# ECG_Schematic.net
KiCad netlist of a schematic drawn in Altium Designer
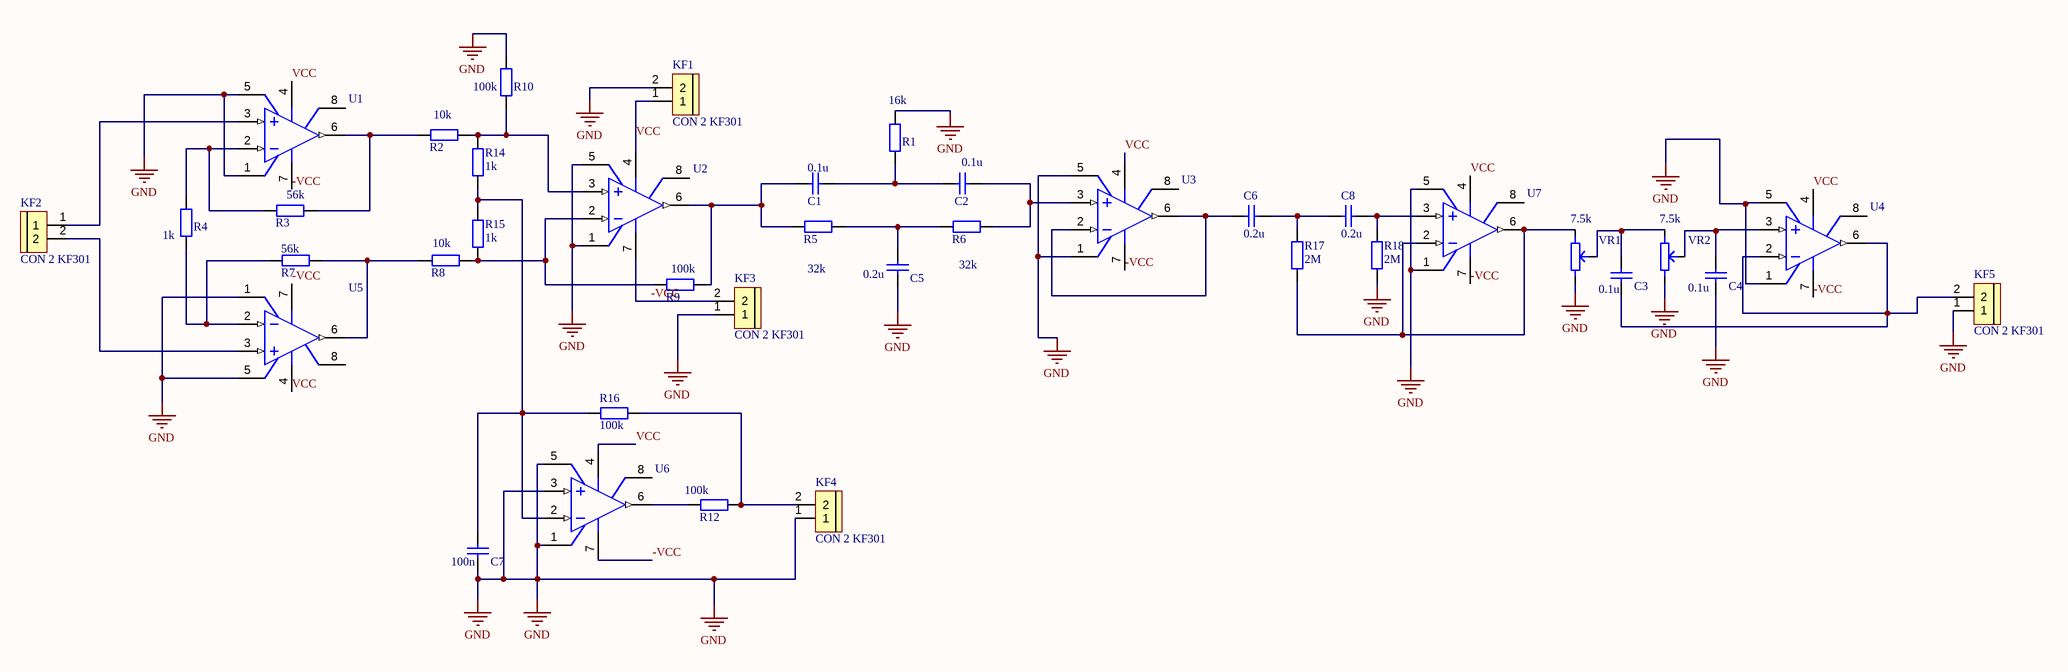
[diagram p0: ECG_Schematic_.SchDoc]

(export (version "E")
  (design (tool "Eeschema 10.0.6"))
  (components
    (comp (ref "C1")
      (value "0.1u")
      (footprint "tu gom")
      (description "C?m")
      (libsource (lib "Ho Chi Minh University of Technology") (part "Tu tantalum 47nF 50V 20 DIP5.08"))
    )
    (comp (ref "C2")
      (value "0.1u")
      (footprint "tu gom")
      (description "C?m")
      (libsource (lib "Ho Chi Minh University of Technology") (part "Tu tantalum 47nF 50V 20 DIP5.08"))
    )
    (comp (ref "C3")
      (value "0.1u")
      (footprint "tu gom")
      (description "C?m")
      (libsource (lib "Ho Chi Minh University of Technology") (part "Tu tantalum 47nF 50V 20 DIP5.08"))
    )
    (comp (ref "C4")
      (value "0.1u")
      (footprint "tu gom")
      (description "C?m")
      (libsource (lib "Ho Chi Minh University of Technology") (part "Tu tantalum 47nF 50V 20 DIP5.08"))
    )
    (comp (ref "C5")
      (value "0.2u")
      (footprint "tu gom")
      (description "C?m")
      (libsource (lib "Ho Chi Minh University of Technology") (part "Tu tantalum 47nF 50V 20 DIP5.08"))
    )
    (comp (ref "C6")
      (value "0.2u")
      (footprint "tu gom")
      (description "C?m")
      (libsource (lib "Ho Chi Minh University of Technology") (part "Tu tantalum 47nF 50V 20 DIP5.08"))
    )
    (comp (ref "C7")
      (value "100n")
      (footprint "tu gom")
      (description "C?m")
      (libsource (lib "Ho Chi Minh University of Technology") (part "Tu tantalum 47nF 50V 20 DIP5.08"))
    )
    (comp (ref "C8")
      (value "0.2u")
      (footprint "tu gom")
      (description "C?m")
      (libsource (lib "Ho Chi Minh University of Technology") (part "Tu tantalum 47nF 50V 20 DIP5.08"))
    )
    (comp (ref "KF1")
      (value "CON 2 KF301")
      (footprint "Con 2 KF301 5.08")
      (description "C?m")
      (libsource (lib "") (part "CON 2 KF7.62_1"))
    )
    (comp (ref "KF2")
      (value "CON 2 KF301")
      (footprint "Con 2 KF301 5.08")
      (description "C?m")
      (libsource (lib "Ho Chi Minh University of Technology") (part "CON 2 KF7.62"))
    )
    (comp (ref "KF3")
      (value "CON 2 KF301")
      (footprint "Con 2 KF301 5.08")
      (description "C?m")
      (libsource (lib "") (part "CON 2 KF7.62_1"))
    )
    (comp (ref "KF4")
      (value "CON 2 KF301")
      (footprint "Con 2 KF301 5.08")
      (description "Cắm")
      (libsource (lib "Connector") (part "CON 2 KF301"))
    )
    (comp (ref "KF5")
      (value "CON 2 KF301")
      (footprint "Con 2 KF301 5.08")
      (description "Cắm")
      (libsource (lib "Connector") (part "CON 2 KF301"))
    )
    (comp (ref "R1")
      (value "16k")
      (footprint "tro vach 1/4w")
      (description "C?m")
      (libsource (lib "Ho Chi Minh University of Technology") (part "Tro Vach 1/4W 5 0.11R"))
    )
    (comp (ref "R2")
      (value "10k")
      (footprint "tro vach 1/4w")
      (description "C?m")
      (libsource (lib "Ho Chi Minh University of Technology") (part "Tro Vach 1/4W 5 0.11R"))
    )
    (comp (ref "R3")
      (value "56k")
      (footprint "tro vach 1/4w")
      (description "C?m")
      (libsource (lib "Ho Chi Minh University of Technology") (part "Tro Vach 1/4W 5 0.11R"))
    )
    (comp (ref "R4")
      (value "1k")
      (footprint "tro vach 1/4w")
      (description "C?m")
      (libsource (lib "Ho Chi Minh University of Technology") (part "Tro Vach 1/4W 5 0.11R"))
    )
    (comp (ref "R5")
      (value "32k")
      (footprint "tro vach 1/4w")
      (description "C?m")
      (libsource (lib "Ho Chi Minh University of Technology") (part "Tro Vach 1/4W 5 0.11R"))
    )
    (comp (ref "R6")
      (value "32k")
      (footprint "tro vach 1/4w")
      (description "C?m")
      (libsource (lib "Ho Chi Minh University of Technology") (part "Tro Vach 1/4W 5 0.11R"))
    )
    (comp (ref "R7")
      (value "56k")
      (footprint "tro vach 1/4w")
      (description "C?m")
      (libsource (lib "Ho Chi Minh University of Technology") (part "Tro Vach 1/4W 5 0.11R"))
    )
    (comp (ref "R8")
      (value "10k")
      (footprint "tro vach 1/4w")
      (description "C?m")
      (libsource (lib "Ho Chi Minh University of Technology") (part "Tro Vach 1/4W 5 0.11R"))
    )
    (comp (ref "R9")
      (value "100k")
      (footprint "tro vach 1/4w")
      (description "C?m")
      (libsource (lib "Ho Chi Minh University of Technology") (part "Tro Vach 1/4W 5 0.11R"))
    )
    (comp (ref "R10")
      (value "100k")
      (footprint "tro vach 1/4w")
      (description "C?m")
      (libsource (lib "Ho Chi Minh University of Technology") (part "Tro Vach 1/4W 5 0.11R"))
    )
    (comp (ref "R12")
      (value "100k")
      (footprint "tro vach 1/4w")
      (description "C?m")
      (libsource (lib "Ho Chi Minh University of Technology") (part "Tro Vach 1/4W 5 0.11R"))
    )
    (comp (ref "R14")
      (value "1k")
      (footprint "tro vach 1/4w")
      (description "Cắm")
      (libsource (lib "Dien Tro") (part "Tro Vach 1/4W 1% 3k"))
    )
    (comp (ref "R15")
      (value "1k")
      (footprint "tro vach 1/4w")
      (description "Cắm")
      (libsource (lib "Dien Tro") (part "Tro Vach 1/4W 1% 3k"))
    )
    (comp (ref "R16")
      (value "100k")
      (footprint "tro vach 1/4w")
      (description "Cắm")
      (libsource (lib "Dien Tro") (part "Tro Vach 1/4W 1% 3k"))
    )
    (comp (ref "R17")
      (value "2M")
      (footprint "tro vach 1/4w")
      (description "C?m")
      (libsource (lib "Ho Chi Minh University of Technology") (part "Tro Vach 1/4W 5 0.11R"))
    )
    (comp (ref "R18")
      (value "2M")
      (footprint "tro vach 1/4w")
      (description "C?m")
      (libsource (lib "Ho Chi Minh University of Technology") (part "Tro Vach 1/4W 5 0.11R"))
    )
    (comp (ref "U1")
      (value "LM741CN/NOPB")
      (footprint "P0008A")
      (description "Operational Amplifier, 8-pin MDIP, Pb-Free")
      (fields (field (name "MANUFACTURER") "Texas Instruments"))
      (libsource (lib "Altium Content Vault") (part "AMP-OPA-LM741-8"))
    )
    (comp (ref "U2")
      (value "LM741CN/NOPB")
      (footprint "P0008A")
      (description "Operational Amplifier, 8-pin MDIP, Pb-Free")
      (fields (field (name "MANUFACTURER") "Texas Instruments"))
      (libsource (lib "Altium Content Vault") (part "AMP-OPA-LM741-8"))
    )
    (comp (ref "U3")
      (value "LM741CN/NOPB")
      (footprint "P0008A")
      (description "Operational Amplifier, 8-pin MDIP, Pb-Free")
      (fields (field (name "MANUFACTURER") "Texas Instruments"))
      (libsource (lib "Altium Content Vault") (part "AMP-OPA-LM741-8"))
    )
    (comp (ref "U4")
      (value "LM741CN/NOPB")
      (footprint "P0008A")
      (description "Operational Amplifier, 8-pin MDIP, Pb-Free")
      (fields (field (name "MANUFACTURER") "Texas Instruments"))
      (libsource (lib "Altium Content Vault") (part "AMP-OPA-LM741-8"))
    )
    (comp (ref "U5")
      (value "B")
      (footprint "P0008A")
      (description "Operational Amplifier, 8-pin MDIP, Pb-Free")
      (fields (field (name "MANUFACTURER") "Texas Instruments"))
      (libsource (lib "Altium Content Vault") (part "AMP-OPA-LM741-8"))
    )
    (comp (ref "U6")
      (value "B")
      (footprint "P0008A")
      (description "Operational Amplifier, 8-pin MDIP, Pb-Free")
      (fields (field (name "MANUFACTURER") "Texas Instruments"))
      (libsource (lib "Altium Content Vault") (part "AMP-OPA-LM741-8"))
    )
    (comp (ref "U7")
      (value "LM741CN/NOPB")
      (footprint "P0008A")
      (description "Operational Amplifier, 8-pin MDIP, Pb-Free")
      (fields (field (name "MANUFACTURER") "Texas Instruments"))
      (libsource (lib "Altium Content Vault") (part "AMP-OPA-LM741-8"))
    )
    (comp (ref "VR1")
      (value "7.5k")
      (footprint "Bien Tro Tam Giac Nam")
      (description "C?m")
      (libsource (lib "Ho Chi Minh University of Technology") (part "Bien tro tam giac 20K Dung"))
    )
    (comp (ref "VR2")
      (value "7.5k")
      (footprint "Bien Tro Tam Giac Nam")
      (description "C?m")
      (libsource (lib "Ho Chi Minh University of Technology") (part "Bien tro tam giac 20K Dung"))
    )
  )
  (nets
    (net (code "1") (name "/-VCC") (class "Default")
      (node (ref "KF3") (pin "2") (pinfunction "2_2") (pintype "passive"))
      (node (ref "U1") (pin "7") (pinfunction "V+_7") (pintype "power_in"))
      (node (ref "U2") (pin "7") (pinfunction "V+_7") (pintype "power_in"))
      (node (ref "U3") (pin "7") (pinfunction "V+_7") (pintype "power_in"))
      (node (ref "U4") (pin "7") (pinfunction "V+_7") (pintype "power_in"))
      (node (ref "U5") (pin "7") (pinfunction "V+_7") (pintype "power_in"))
      (node (ref "U6") (pin "7") (pinfunction "V+_7") (pintype "power_in"))
      (node (ref "U7") (pin "7") (pinfunction "V+_7") (pintype "power_in"))
    )
    (net (code "2") (name "/VCC") (class "Default")
      (node (ref "KF1") (pin "1") (pinfunction "1_1") (pintype "passive"))
      (node (ref "U1") (pin "4") (pinfunction "V-_4") (pintype "power_in"))
      (node (ref "U2") (pin "4") (pinfunction "V-_4") (pintype "power_in"))
      (node (ref "U3") (pin "4") (pinfunction "V-_4") (pintype "power_in"))
      (node (ref "U4") (pin "4") (pinfunction "V-_4") (pintype "power_in"))
      (node (ref "U5") (pin "4") (pinfunction "V-_4") (pintype "power_in"))
      (node (ref "U6") (pin "4") (pinfunction "V-_4") (pintype "power_in"))
      (node (ref "U7") (pin "4") (pinfunction "V-_4") (pintype "power_in"))
    )
    (net (code "3") (name "GND") (class "Default")
      (node (ref "C4") (pin "2") (pinfunction "2_2") (pintype "passive"))
      (node (ref "C5") (pin "2") (pinfunction "2_2") (pintype "passive"))
      (node (ref "C7") (pin "2") (pinfunction "2_2") (pintype "passive"))
      (node (ref "KF1") (pin "2") (pinfunction "2_2") (pintype "passive"))
      (node (ref "KF3") (pin "1") (pinfunction "1_1") (pintype "passive"))
      (node (ref "KF4") (pin "1") (pinfunction "1_1") (pintype "passive"))
      (node (ref "KF5") (pin "1") (pinfunction "1_1") (pintype "passive"))
      (node (ref "R1") (pin "2") (pinfunction "2_2") (pintype "passive"))
      (node (ref "R10") (pin "2") (pinfunction "2_2") (pintype "passive"))
      (node (ref "R18") (pin "1") (pinfunction "1_1") (pintype "passive"))
      (node (ref "U1") (pin "1") (pinfunction "OFS_NULL_1") (pintype "passive"))
      (node (ref "U1") (pin "5") (pinfunction "OFS_NULL_5") (pintype "passive"))
      (node (ref "U2") (pin "1") (pinfunction "OFS_NULL_1") (pintype "passive"))
      (node (ref "U2") (pin "5") (pinfunction "OFS_NULL_5") (pintype "passive"))
      (node (ref "U3") (pin "1") (pinfunction "OFS_NULL_1") (pintype "passive"))
      (node (ref "U3") (pin "5") (pinfunction "OFS_NULL_5") (pintype "passive"))
      (node (ref "U4") (pin "1") (pinfunction "OFS_NULL_1") (pintype "passive"))
      (node (ref "U4") (pin "5") (pinfunction "OFS_NULL_5") (pintype "passive"))
      (node (ref "U5") (pin "1") (pinfunction "OFS_NULL_1") (pintype "passive"))
      (node (ref "U5") (pin "5") (pinfunction "OFS_NULL_5") (pintype "passive"))
      (node (ref "U6") (pin "1") (pinfunction "OFS_NULL_1") (pintype "passive"))
      (node (ref "U6") (pin "3") (pinfunction "IN+_3") (pintype "input"))
      (node (ref "U6") (pin "5") (pinfunction "OFS_NULL_5") (pintype "passive"))
      (node (ref "U7") (pin "1") (pinfunction "OFS_NULL_1") (pintype "passive"))
      (node (ref "U7") (pin "5") (pinfunction "OFS_NULL_5") (pintype "passive"))
      (node (ref "VR1") (pin "3") (pinfunction "3_3") (pintype "passive"))
      (node (ref "VR2") (pin "3") (pinfunction "3_3") (pintype "passive"))
    )
    (net (code "4") (name "Net-(C1-Pad1)") (class "Default")
      (node (ref "C1") (pin "1") (pinfunction "1_1") (pintype "passive"))
      (node (ref "C2") (pin "2") (pinfunction "2_2") (pintype "passive"))
      (node (ref "R1") (pin "1") (pinfunction "1_1") (pintype "passive"))
    )
    (net (code "5") (name "Net-(C3-Pad1)") (class "Default")
      (node (ref "C3") (pin "1") (pinfunction "1_1") (pintype "passive"))
      (node (ref "VR1") (pin "2") (pinfunction "2_2") (pintype "passive"))
      (node (ref "VR2") (pin "1") (pinfunction "1_1") (pintype "passive"))
    )
    (net (code "6") (name "Net-(C5-Pad1)") (class "Default")
      (node (ref "C5") (pin "1") (pinfunction "1_1") (pintype "passive"))
      (node (ref "R5") (pin "2") (pinfunction "2_2") (pintype "passive"))
      (node (ref "R6") (pin "1") (pinfunction "1_1") (pintype "passive"))
    )
    (net (code "7") (name "Net-(C6-Pad2)") (class "Default")
      (node (ref "C6") (pin "2") (pinfunction "2_2") (pintype "passive"))
      (node (ref "C8") (pin "1") (pinfunction "1_1") (pintype "passive"))
      (node (ref "R17") (pin "2") (pinfunction "2_2") (pintype "passive"))
    )
    (net (code "8") (name "Net-(KF4-Pad2)") (class "Default")
      (node (ref "KF4") (pin "2") (pinfunction "2_2") (pintype "passive"))
      (node (ref "R12") (pin "1") (pinfunction "1_1") (pintype "passive"))
      (node (ref "R16") (pin "2") (pinfunction "2_2") (pintype "passive"))
    )
    (net (code "9") (name "Net-(U1-IN+)") (class "Default")
      (node (ref "KF2") (pin "1") (pinfunction "1_1") (pintype "passive"))
      (node (ref "U1") (pin "3") (pinfunction "IN+_3") (pintype "input"))
    )
    (net (code "10") (name "Net-(U1-IN-)") (class "Default")
      (node (ref "R3") (pin "1") (pinfunction "1_1") (pintype "passive"))
      (node (ref "R4") (pin "2") (pinfunction "2_2") (pintype "passive"))
      (node (ref "U1") (pin "2") (pinfunction "IN-_2") (pintype "input"))
    )
    (net (code "11") (name "Net-(U1-OUT)") (class "Default")
      (node (ref "R2") (pin "1") (pinfunction "1_1") (pintype "passive"))
      (node (ref "R3") (pin "2") (pinfunction "2_2") (pintype "passive"))
      (node (ref "U1") (pin "6") (pinfunction "OUT_6") (pintype "output"))
    )
    (net (code "12") (name "Net-(U2-IN+)") (class "Default")
      (node (ref "R10") (pin "1") (pinfunction "1_1") (pintype "passive"))
      (node (ref "R14") (pin "2") (pinfunction "2_2") (pintype "passive"))
      (node (ref "R2") (pin "2") (pinfunction "2_2") (pintype "passive"))
      (node (ref "U2") (pin "3") (pinfunction "IN+_3") (pintype "input"))
    )
    (net (code "13") (name "Net-(U2-IN-)") (class "Default")
      (node (ref "R15") (pin "1") (pinfunction "1_1") (pintype "passive"))
      (node (ref "R8") (pin "2") (pinfunction "2_2") (pintype "passive"))
      (node (ref "R9") (pin "1") (pinfunction "1_1") (pintype "passive"))
      (node (ref "U2") (pin "2") (pinfunction "IN-_2") (pintype "input"))
    )
    (net (code "14") (name "Net-(U2-OUT)") (class "Default")
      (node (ref "C1") (pin "2") (pinfunction "2_2") (pintype "passive"))
      (node (ref "R5") (pin "1") (pinfunction "1_1") (pintype "passive"))
      (node (ref "R9") (pin "2") (pinfunction "2_2") (pintype "passive"))
      (node (ref "U2") (pin "6") (pinfunction "OUT_6") (pintype "output"))
    )
    (net (code "15") (name "Net-(U3-IN+)") (class "Default")
      (node (ref "C2") (pin "1") (pinfunction "1_1") (pintype "passive"))
      (node (ref "R6") (pin "2") (pinfunction "2_2") (pintype "passive"))
      (node (ref "U3") (pin "3") (pinfunction "IN+_3") (pintype "input"))
    )
    (net (code "16") (name "Net-(U3-IN-)") (class "Default")
      (node (ref "C6") (pin "1") (pinfunction "1_1") (pintype "passive"))
      (node (ref "U3") (pin "2") (pinfunction "IN-_2") (pintype "input"))
      (node (ref "U3") (pin "6") (pinfunction "OUT_6") (pintype "output"))
    )
    (net (code "17") (name "Net-(U4-IN+)") (class "Default")
      (node (ref "C4") (pin "1") (pinfunction "1_1") (pintype "passive"))
      (node (ref "U4") (pin "3") (pinfunction "IN+_3") (pintype "input"))
      (node (ref "VR2") (pin "2") (pinfunction "2_2") (pintype "passive"))
    )
    (net (code "18") (name "Net-(U4-IN-)") (class "Default")
      (node (ref "C3") (pin "2") (pinfunction "2_2") (pintype "passive"))
      (node (ref "KF5") (pin "2") (pinfunction "2_2") (pintype "passive"))
      (node (ref "U4") (pin "2") (pinfunction "IN-_2") (pintype "input"))
      (node (ref "U4") (pin "6") (pinfunction "OUT_6") (pintype "output"))
    )
    (net (code "19") (name "Net-(U5-IN+)") (class "Default")
      (node (ref "KF2") (pin "2") (pinfunction "2_2") (pintype "passive"))
      (node (ref "U5") (pin "3") (pinfunction "IN+_3") (pintype "input"))
    )
    (net (code "20") (name "Net-(U5-IN-)") (class "Default")
      (node (ref "R4") (pin "1") (pinfunction "1_1") (pintype "passive"))
      (node (ref "R7") (pin "1") (pinfunction "1_1") (pintype "passive"))
      (node (ref "U5") (pin "2") (pinfunction "IN-_2") (pintype "input"))
    )
    (net (code "21") (name "Net-(U5-OUT)") (class "Default")
      (node (ref "R7") (pin "2") (pinfunction "2_2") (pintype "passive"))
      (node (ref "R8") (pin "1") (pinfunction "1_1") (pintype "passive"))
      (node (ref "U5") (pin "6") (pinfunction "OUT_6") (pintype "output"))
    )
    (net (code "22") (name "Net-(U6-IN-)") (class "Default")
      (node (ref "C7") (pin "1") (pinfunction "1_1") (pintype "passive"))
      (node (ref "R14") (pin "1") (pinfunction "1_1") (pintype "passive"))
      (node (ref "R15") (pin "2") (pinfunction "2_2") (pintype "passive"))
      (node (ref "R16") (pin "1") (pinfunction "1_1") (pintype "passive"))
      (node (ref "U6") (pin "2") (pinfunction "IN-_2") (pintype "input"))
    )
    (net (code "23") (name "Net-(U6-OUT)") (class "Default")
      (node (ref "R12") (pin "2") (pinfunction "2_2") (pintype "passive"))
      (node (ref "U6") (pin "6") (pinfunction "OUT_6") (pintype "output"))
    )
    (net (code "24") (name "Net-(U7-IN+)") (class "Default")
      (node (ref "C8") (pin "2") (pinfunction "2_2") (pintype "passive"))
      (node (ref "R18") (pin "2") (pinfunction "2_2") (pintype "passive"))
      (node (ref "U7") (pin "3") (pinfunction "IN+_3") (pintype "input"))
    )
    (net (code "25") (name "Net-(U7-IN-)") (class "Default")
      (node (ref "R17") (pin "1") (pinfunction "1_1") (pintype "passive"))
      (node (ref "U7") (pin "2") (pinfunction "IN-_2") (pintype "input"))
      (node (ref "U7") (pin "6") (pinfunction "OUT_6") (pintype "output"))
      (node (ref "VR1") (pin "1") (pinfunction "1_1") (pintype "passive"))
    )
    (net (code "26") (name "unconnected-(U1-NC-Pad8)") (class "Default")
      (node (ref "U1") (pin "8") (pinfunction "NC_8") (pintype "passive"))
    )
    (net (code "27") (name "unconnected-(U2-NC-Pad8)") (class "Default")
      (node (ref "U2") (pin "8") (pinfunction "NC_8") (pintype "passive"))
    )
    (net (code "28") (name "unconnected-(U3-NC-Pad8)") (class "Default")
      (node (ref "U3") (pin "8") (pinfunction "NC_8") (pintype "passive"))
    )
    (net (code "29") (name "unconnected-(U4-NC-Pad8)") (class "Default")
      (node (ref "U4") (pin "8") (pinfunction "NC_8") (pintype "passive"))
    )
    (net (code "30") (name "unconnected-(U5-NC-Pad8)") (class "Default")
      (node (ref "U5") (pin "8") (pinfunction "NC_8") (pintype "passive"))
    )
    (net (code "31") (name "unconnected-(U6-NC-Pad8)") (class "Default")
      (node (ref "U6") (pin "8") (pinfunction "NC_8") (pintype "passive"))
    )
    (net (code "32") (name "unconnected-(U7-NC-Pad8)") (class "Default")
      (node (ref "U7") (pin "8") (pinfunction "NC_8") (pintype "passive"))
    )
  )
)
